# Sch.net
KiCad netlist of a schematic drawn in Altium Designer
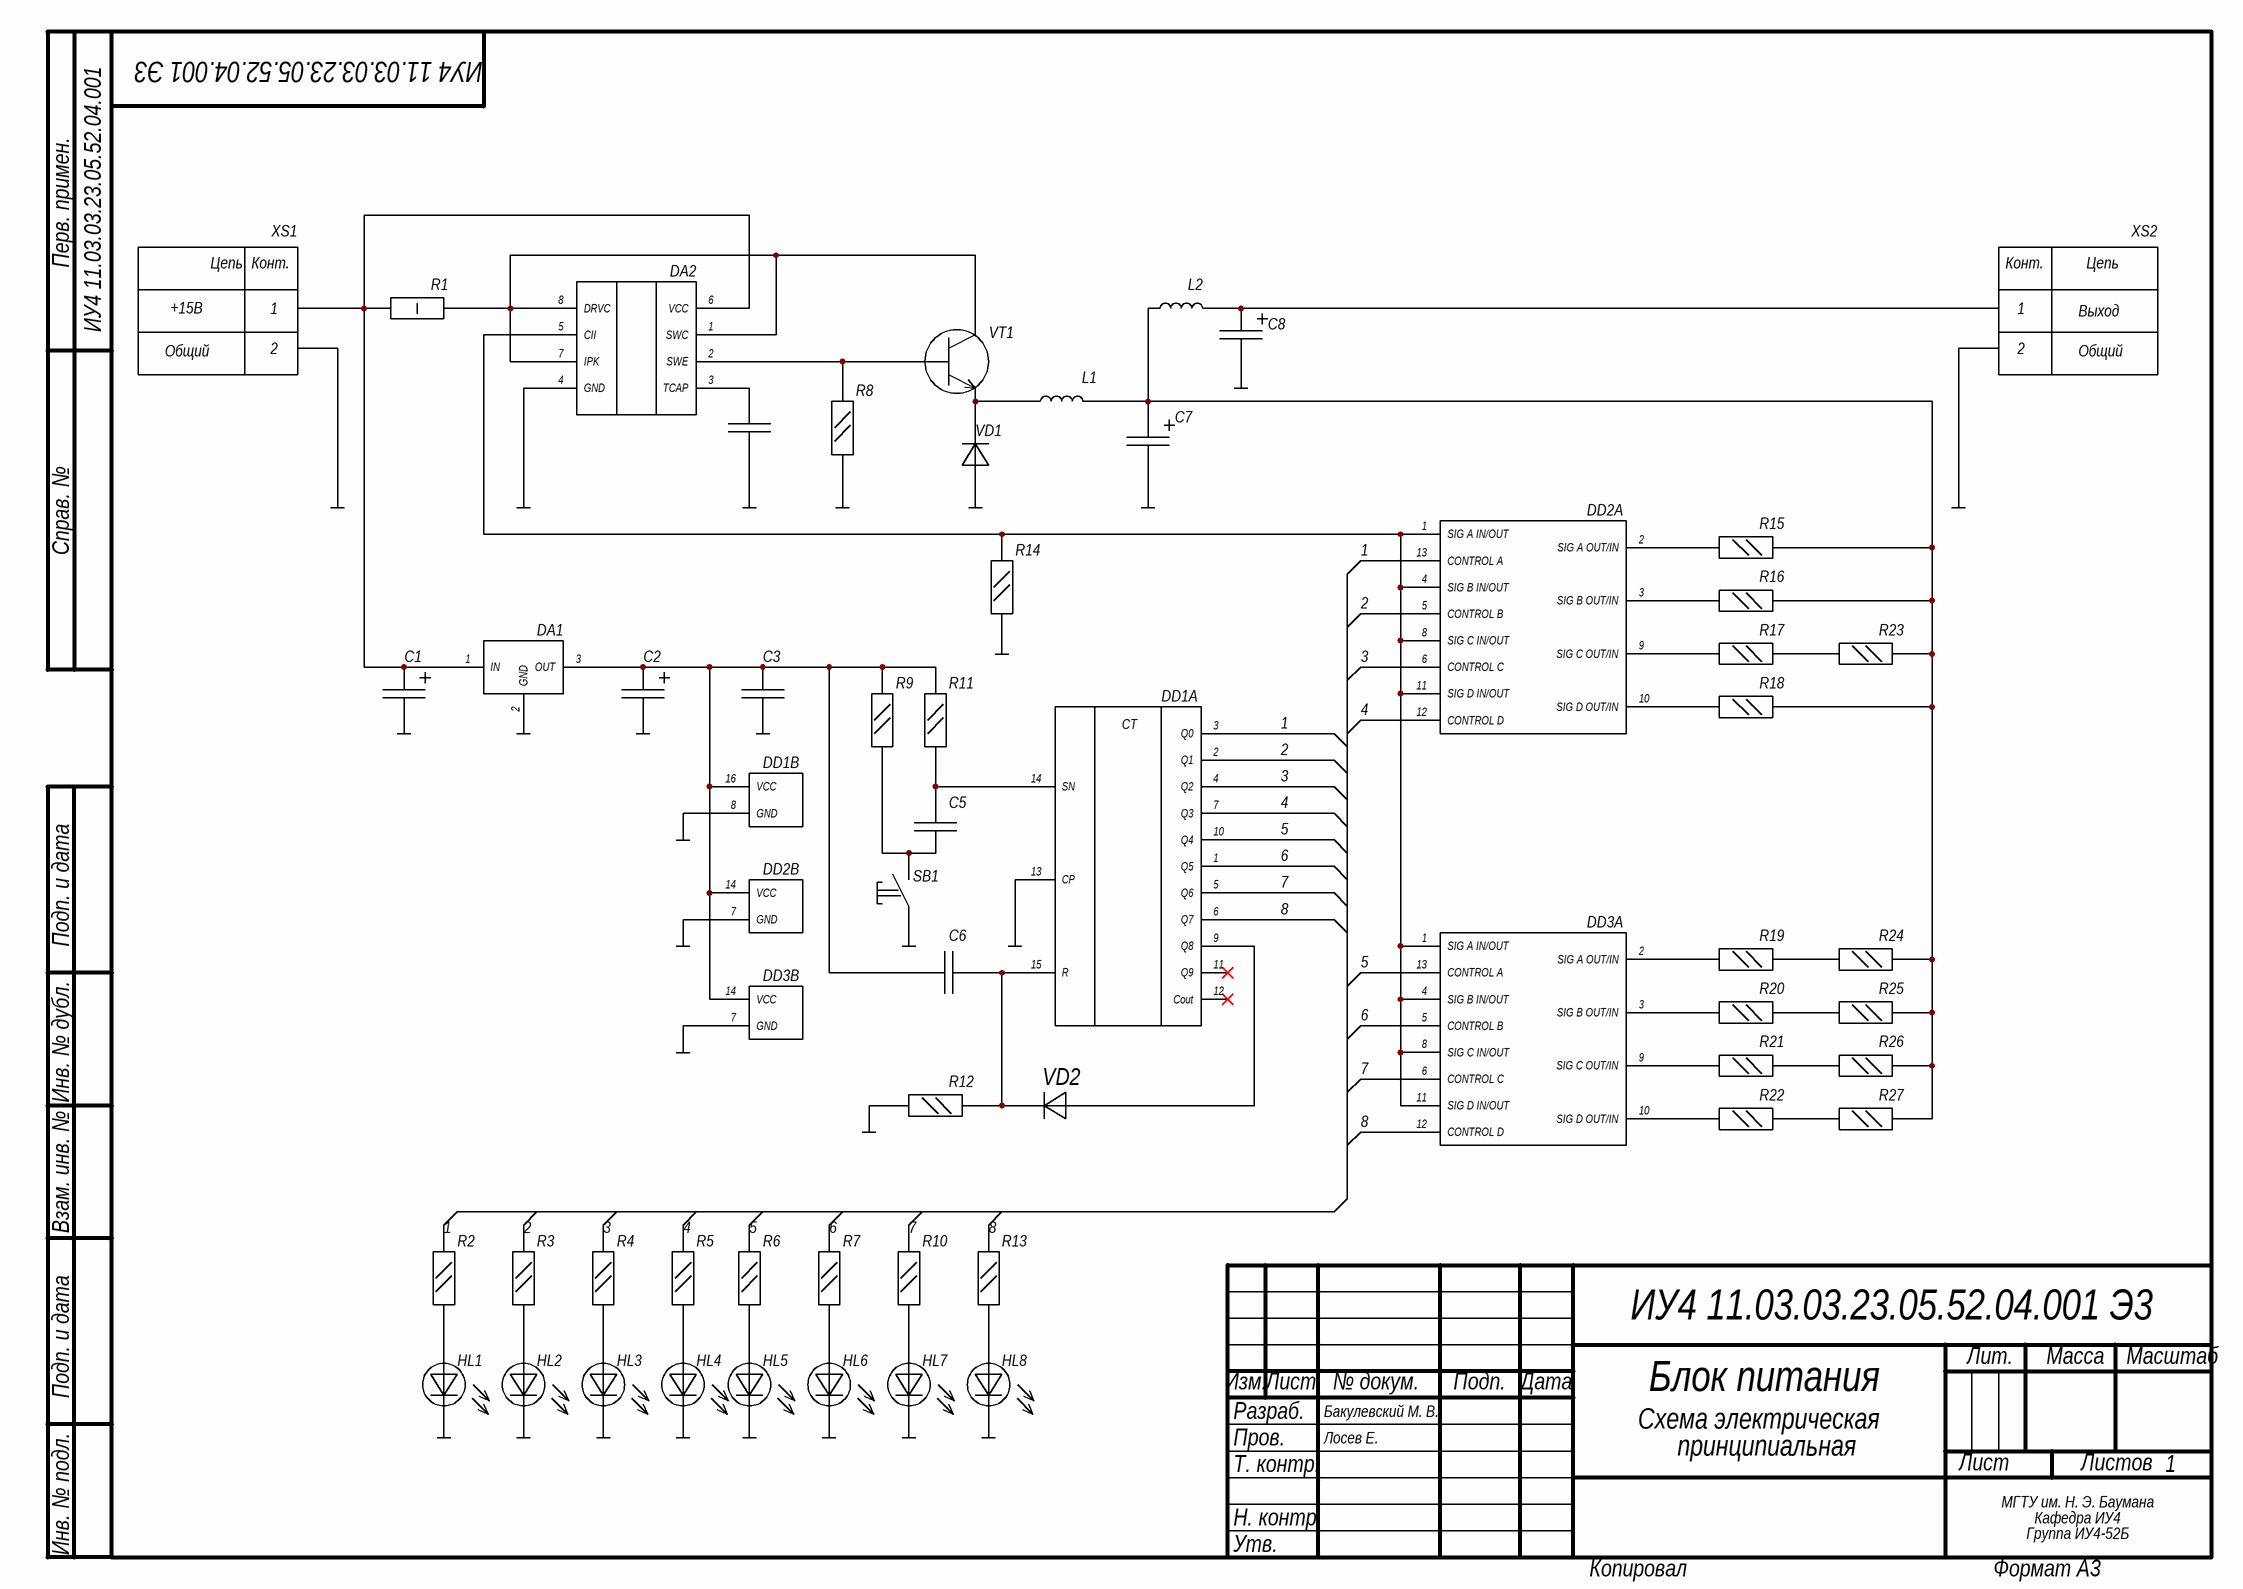
[diagram p0: Sch.SchDoc]

(export (version "E")
  (design (tool "Eeschema 10.0.6"))
  (components
    (comp (ref "C1")
      (value "100uF 25V")
      (footprint "CAPPR250-630X1120")
      (description "ECAP TKR101M1EE11 25В 100мкФ ±5% (Jamicon, Китай)")
      (libsource (lib "Schlib1") (part "Cap Polarity 100uF 25V"))
    )
    (comp (ref "C2")
      (value "100uF 25V")
      (footprint "CAPPR250-630X1120")
      (description "ECAP TKR101M1EE11 25В 100мкФ ±5% (Jamicon, Китай)")
      (libsource (lib "Schlib1") (part "Cap Polarity 100uF 25V"))
    )
    (comp (ref "C3")
      (value "Cap Ceramic 0.1uF")
      (footprint "CAPPRB508-450X850")
      (description "CAP X7R RDER71H104K 25В 0.1мкФ ±10% (Murata, Япония)")
      (libsource (lib "Schlib1") (part "Cap Ceramic 0.1uF"))
    )
    (comp (ref "C4")
      (value "Cap Ceramic 470pF")
      (footprint "CAPPRB508-450X850")
      (description "CAP NPO RDE5C1H471J 25В 470пкФ ±5% (Murata, Япония)")
      (libsource (lib "Schlib1") (part "Cap Ceramic 470pF"))
    )
    (comp (ref "C5")
      (value "Cap Ceramic 0.1uF")
      (footprint "CAPPRB508-450X850")
      (description "CAP X7R RDER71H104K 25В 0.1мкФ ±10% (Murata, Япония)")
      (libsource (lib "Schlib1") (part "Cap Ceramic 0.1uF"))
    )
    (comp (ref "C6")
      (value "Cap Ceramic 0.1uF")
      (footprint "CAPPRB508-450X850")
      (description "CAP X7R RDER71H104K 25В 0.1мкФ ±10% (Murata, Япония)")
      (libsource (lib "Schlib1") (part "Cap Ceramic 0.1uF"))
    )
    (comp (ref "C7")
      (value "470uF 25V")
      (footprint "CAPPR350-850X1300")
      (description "ECAP TKR471M1EF14 25В 470мкФ ±5% (Jamicon, Китай)")
      (libsource (lib "Schlib1") (part "Cap Polarity 470uF 25V"))
    )
    (comp (ref "C8")
      (value "470uF 25V")
      (footprint "CAPPR350-850X1300")
      (description "ECAP TKR471M1EF14 25В 470мкФ ±5% (Jamicon, Китай)")
      (libsource (lib "Schlib1") (part "Cap Polarity 470uF 25V"))
    )
    (comp (ref "DA1")
      (value "L7809ABV")
      (footprint "TO-220AB")
      (description "L7809ABV (STMicroelectronics, Швейцария)")
      (libsource (lib "Schlib1") (part "L7809ABV"))
    )
    (comp (ref "DA2")
      (value "MC34063ABN")
      (footprint "DIPS8-300")
      (description "MC34063ABN (STMicroelectronis, Швейцария)")
      (libsource (lib "Schlib1") (part "MC34063ABN"))
    )
    (comp (ref "DD1")
      (value "CD4017BE")
      (footprint "DIPS16-300")
      (description "CD4017BE (Texas Instuments, США)")
      (libsource (lib "Schlib1") (part "CD4017BE"))
    )
    (comp (ref "DD2")
      (value "CD4066BE")
      (footprint "DIPS14-300")
      (description "CD4066BE (HGSEMI, Китай)")
      (libsource (lib "Schlib1") (part "CD4066BE"))
    )
    (comp (ref "DD3")
      (value "CD4066BE")
      (footprint "DIPS14-300")
      (description "CD4066BE (HGSEMI, Китай)")
      (libsource (lib "Schlib1") (part "CD4066BE"))
    )
    (comp (ref "HL1")
      (value "LED Red")
      (footprint "LD-5mm-R")
      (description "GNL-5012ED (G-nor Electronics, Китай)")
      (libsource (lib "Schlib1") (part "LED Red"))
    )
    (comp (ref "HL2")
      (value "LED Red")
      (footprint "LD-5mm-R")
      (description "GNL-5012ED (G-nor Electronics, Китай)")
      (libsource (lib "Schlib1") (part "LED Red"))
    )
    (comp (ref "HL3")
      (value "LED Red")
      (footprint "LD-5mm-R")
      (description "GNL-5012ED (G-nor Electronics, Китай)")
      (libsource (lib "Schlib1") (part "LED Red"))
    )
    (comp (ref "HL4")
      (value "LED Red")
      (footprint "LD-5mm-R")
      (description "GNL-5012ED (G-nor Electronics, Китай)")
      (libsource (lib "Schlib1") (part "LED Red"))
    )
    (comp (ref "HL5")
      (value "LED Red")
      (footprint "LD-5mm-R")
      (description "GNL-5012ED (G-nor Electronics, Китай)")
      (libsource (lib "Schlib1") (part "LED Red"))
    )
    (comp (ref "HL6")
      (value "LED Red")
      (footprint "LD-5mm-R")
      (description "GNL-5012ED (G-nor Electronics, Китай)")
      (libsource (lib "Schlib1") (part "LED Red"))
    )
    (comp (ref "HL7")
      (value "LED Red")
      (footprint "LD-5mm-R")
      (description "GNL-5012ED (G-nor Electronics, Китай)")
      (libsource (lib "Schlib1") (part "LED Red"))
    )
    (comp (ref "HL8")
      (value "LED Red")
      (footprint "LD-5mm-R")
      (description "GNL-5012ED (G-nor Electronics, Китай)")
      (libsource (lib "Schlib1") (part "LED Red"))
    )
    (comp (ref "L1")
      (value "КИ (КИГ) 3,0−100мкГн ±5%")
      (footprint "INDRD_WURTH_WE-TI")
      (description "КИ (КИГ) 3,0−100мкГн ±10% (Россия)")
      (libsource (lib "Schlib1") (part "Inductor КИ (КИГ) 3,0−100мкГн ±5%"))
    )
    (comp (ref "L2")
      (value "КИ (КИГ) 3,0−100мкГн ±5%")
      (footprint "INDRD_WURTH_WE-TI")
      (description "КИ (КИГ) 3,0−100мкГн ±10% (Россия)")
      (libsource (lib "Schlib1") (part "Inductor КИ (КИГ) 3,0−100мкГн ±5%"))
    )
    (comp (ref "R1")
      (value "0,1Ом")
      (footprint "Res 1W")
      (description "С1-4−1−0,1Ом ±5% (Россия)")
      (libsource (lib "Schlib1") (part "Res 0,1 1W"))
    )
    (comp (ref "R2")
      (value "1кОм")
      (footprint "Res 0.125W")
      (description "С1-4−0,125−1кОм ±5% (Россия)")
      (libsource (lib "Schlib1") (part "Res 1K 0.125W"))
    )
    (comp (ref "R3")
      (value "1кОм")
      (footprint "Res 0.125W")
      (description "С1-4−0,125−1кОм ±5% (Россия)")
      (libsource (lib "Schlib1") (part "Res 1K 0.125W"))
    )
    (comp (ref "R4")
      (value "1кОм")
      (footprint "Res 0.125W")
      (description "С1-4−0,125−1кОм ±5% (Россия)")
      (libsource (lib "Schlib1") (part "Res 1K 0.125W"))
    )
    (comp (ref "R5")
      (value "1кОм")
      (footprint "Res 0.125W")
      (description "С1-4−0,125−1кОм ±5% (Россия)")
      (libsource (lib "Schlib1") (part "Res 1K 0.125W"))
    )
    (comp (ref "R6")
      (value "1кОм")
      (footprint "Res 0.125W")
      (description "С1-4−0,125−1кОм ±5% (Россия)")
      (libsource (lib "Schlib1") (part "Res 1K 0.125W"))
    )
    (comp (ref "R7")
      (value "1кОм")
      (footprint "Res 0.125W")
      (description "С1-4−0,125−1кОм ±5% (Россия)")
      (libsource (lib "Schlib1") (part "Res 1K 0.125W"))
    )
    (comp (ref "R8")
      (value "22кОм")
      (footprint "Res 0.125W")
      (description "С1-4−0,125−22кОм ±5% (Россия)")
      (libsource (lib "Schlib1") (part "Res 22K 0.125W"))
    )
    (comp (ref "R9")
      (value "100кОм")
      (footprint "Res 0.125W")
      (description "С1-4−0,125−100кОм ±5% (Россия)")
      (libsource (lib "Schlib1") (part "Res 100K 0.125W"))
    )
    (comp (ref "R10")
      (value "1кОм")
      (footprint "Res 0.125W")
      (description "С1-4−0,125−1кОм ±5% (Россия)")
      (libsource (lib "Schlib1") (part "Res 1K 0.125W"))
    )
    (comp (ref "R11")
      (value "100кОм")
      (footprint "Res 0.125W")
      (description "С1-4−0,125−100кОм ±5% (Россия)")
      (libsource (lib "Schlib1") (part "Res 100K 0.125W"))
    )
    (comp (ref "R12")
      (value "100кОм")
      (footprint "Res 0.125W")
      (description "С1-4−0,125−100кОм ±5% (Россия)")
      (libsource (lib "Schlib1") (part "Res 100K 0.125W"))
    )
    (comp (ref "R13")
      (value "1кОм")
      (footprint "Res 0.125W")
      (description "С1-4−0,125−1кОм ±5% (Россия)")
      (libsource (lib "Schlib1") (part "Res 1K 0.125W"))
    )
    (comp (ref "R14")
      (value "1кОм")
      (footprint "Res 0.125W")
      (description "С1-4−0,125−1,5кОм ±5% (Россия)")
      (libsource (lib "Schlib1") (part "Res 1,5K 0.125W"))
    )
    (comp (ref "R15")
      (value "270Ом")
      (footprint "Res 0.125W")
      (description "С1-4−0,125−270Ом ±5% (Россия)")
      (libsource (lib "Schlib1") (part "Res 270 0.125W"))
    )
    (comp (ref "R16")
      (value "1кОм")
      (footprint "Res 0.125W")
      (description "С1-4−0,125−1,5кОм ±5% (Россия)")
      (libsource (lib "Schlib1") (part "Res 1,5K 0.125W"))
    )
    (comp (ref "R17")
      (value "2кОм")
      (footprint "Res 0.125W")
      (description "С1-4−0,125−2кОм ±5% (Россия)")
      (libsource (lib "Schlib1") (part "Res 2K 0.125W"))
    )
    (comp (ref "R18")
      (value "3,9кОм")
      (footprint "Res 0.125W")
      (description "С1-4−0,125−3,9кОм ±5% (Россия)")
      (libsource (lib "Schlib1") (part "Res 3,9K 0.125W"))
    )
    (comp (ref "R19")
      (value "4,3кОм")
      (footprint "Res 0.125W")
      (description "С1-4−0,125−4,3кОм ±5% (Россия)")
      (libsource (lib "Schlib1") (part "Res 4,3K 0.125W"))
    )
    (comp (ref "R20")
      (value "5,6кОм")
      (footprint "Res 0.125W")
      (description "С1-4−0,125−5,6кОм ±5% (Россия)")
      (libsource (lib "Schlib1") (part "Res 5,6K 0.125W"))
    )
    (comp (ref "R21")
      (value "7,5кОм")
      (footprint "Res 0.125W")
      (description "С1-4−0,125−7,5кОм ±5% (Россия)")
      (libsource (lib "Schlib1") (part "Res 7,5K 0.125W"))
    )
    (comp (ref "R22")
      (value "9,1кОм")
      (footprint "Res 0.125W")
      (description "С1-4−0,125−9,1кОм ±5% (Россия)")
      (libsource (lib "Schlib1") (part "Res 9,1K 0.125W"))
    )
    (comp (ref "R23")
      (value "100Ом")
      (footprint "Res 0.125W")
      (description "С1-4−0,125−100Ом ±5% (Россия)")
      (libsource (lib "Schlib1") (part "Res 100 0.125W"))
    )
    (comp (ref "R24")
      (value "200Ом")
      (footprint "Res 0.125W")
      (description "С1-4−0,125−200Ом ±5% (Россия)")
      (libsource (lib "Schlib1") (part "Res 200 0.125W"))
    )
    (comp (ref "R25")
      (value "200Ом")
      (footprint "Res 0.125W")
      (description "С1-4−0,125−200Ом ±5% (Россия)")
      (libsource (lib "Schlib1") (part "Res 200 0.125W"))
    )
    (comp (ref "R26")
      (value "100Ом")
      (footprint "Res 0.125W")
      (description "С1-4−0,125−100Ом ±5% (Россия)")
      (libsource (lib "Schlib1") (part "Res 100 0.125W"))
    )
    (comp (ref "R27")
      (value "300Ом")
      (footprint "Res 0.125W")
      (description "С1-4−0,125−300Ом ±5% (Россия)")
      (libsource (lib "Schlib1") (part "Res 300 0.125W"))
    )
    (comp (ref "SB1")
      (value "Button SMD")
      (footprint "Button SMD")
      (description "Кнопка тактовая 1437566-3 (TE Connectivity, США)")
      (libsource (lib "Schlib1") (part "Button"))
    )
    (comp (ref "VD1")
      (value "1N5820")
      (footprint "DO-27")
      (description "1N5820 (Diotec, Германия)")
      (libsource (lib "Schlib1") (part "Diode 1N5820"))
    )
    (comp (ref "VD2")
      (value "1N4002")
      (footprint "DO-35")
      (description "1N4148 (Diotec, Германия)")
      (fields (field (name "PUBLISHER") "Andrew Danich"))
      (libsource (lib "Schlib1") (part "Diode 1N4148"))
    )
    (comp (ref "VT1")
      (value "TIP121G")
      (footprint "TO-220AB")
      (description "TIP121G (ON Semiconductor, США)")
      (libsource (lib "Schlib1") (part "Transistor TIP121G"))
    )
    (comp (ref "XS1")
      (value "Power Connector 2 pin")
      (footprint "WIELAND_25.161.0253.0")
      (description "25.161.0253.0 (Wieland Electric, Германия)")
      (libsource (lib "Schlib1") (part "Power Connector 2 pin"))
    )
    (comp (ref "XS2")
      (value "Power Connector 2 pin")
      (footprint "WIELAND_25.161.0253.0")
      (description "25.161.0253.0 (Wieland Electric, Германия)")
      (libsource (lib "Schlib1") (part "Power Connector 2 pin"))
    )
  )
  (nets
    (net (code "1") (name "/1") (class "Default")
      (node (ref "DD1") (pin "3") (pinfunction "Q0_3") (pintype "passive"))
      (node (ref "DD2") (pin "13") (pinfunction "CONTROL_A_13") (pintype "passive"))
    )
    (net (code "2") (name "/2") (class "Default")
      (node (ref "DD1") (pin "2") (pinfunction "Q1_2") (pintype "passive"))
      (node (ref "DD2") (pin "5") (pinfunction "CONTROL_B_5") (pintype "passive"))
    )
    (net (code "3") (name "/3") (class "Default")
      (node (ref "DD1") (pin "4") (pinfunction "Q2_4") (pintype "passive"))
      (node (ref "DD2") (pin "6") (pinfunction "CONTROL_C_6") (pintype "passive"))
    )
    (net (code "4") (name "/4") (class "Default")
      (node (ref "DD1") (pin "7") (pinfunction "Q3_7") (pintype "passive"))
      (node (ref "DD2") (pin "12") (pinfunction "CONTROL_D_12") (pintype "passive"))
    )
    (net (code "5") (name "/5") (class "Default")
      (node (ref "DD1") (pin "10") (pinfunction "Q4_10") (pintype "passive"))
      (node (ref "DD3") (pin "13") (pinfunction "CONTROL_A_13") (pintype "passive"))
    )
    (net (code "6") (name "/6") (class "Default")
      (node (ref "DD1") (pin "1") (pinfunction "Q5_1") (pintype "passive"))
      (node (ref "DD3") (pin "5") (pinfunction "CONTROL_B_5") (pintype "passive"))
    )
    (net (code "7") (name "/7") (class "Default")
      (node (ref "DD1") (pin "5") (pinfunction "Q6_5") (pintype "passive"))
      (node (ref "DD3") (pin "6") (pinfunction "CONTROL_C_6") (pintype "passive"))
    )
    (net (code "8") (name "/8") (class "Default")
      (node (ref "DD1") (pin "6") (pinfunction "Q7_6") (pintype "passive"))
      (node (ref "DD3") (pin "12") (pinfunction "CONTROL_D_12") (pintype "passive"))
    )
    (net (code "9") (name "GND") (class "Default")
      (node (ref "C1") (pin "2") (pinfunction "2_2") (pintype "passive"))
      (node (ref "C2") (pin "2") (pinfunction "2_2") (pintype "passive"))
      (node (ref "C3") (pin "2") (pinfunction "2_2") (pintype "passive"))
      (node (ref "C4") (pin "2") (pinfunction "2_2") (pintype "passive"))
      (node (ref "C7") (pin "2") (pinfunction "2_2") (pintype "passive"))
      (node (ref "C8") (pin "2") (pinfunction "2_2") (pintype "passive"))
      (node (ref "DA1") (pin "2") (pinfunction "GND_2") (pintype "passive"))
      (node (ref "DA2") (pin "4") (pinfunction "GND_4") (pintype "passive"))
      (node (ref "DD1") (pin "13") (pinfunction "CP_13") (pintype "passive"))
      (node (ref "DD1") (pin "8") (pinfunction "GND_8") (pintype "passive"))
      (node (ref "DD2") (pin "7") (pinfunction "GND_7") (pintype "passive"))
      (node (ref "DD3") (pin "7") (pinfunction "GND_7") (pintype "passive"))
      (node (ref "HL1") (pin "2") (pinfunction "K_2") (pintype "passive"))
      (node (ref "HL2") (pin "2") (pinfunction "K_2") (pintype "passive"))
      (node (ref "HL3") (pin "2") (pinfunction "K_2") (pintype "passive"))
      (node (ref "HL4") (pin "2") (pinfunction "K_2") (pintype "passive"))
      (node (ref "HL5") (pin "2") (pinfunction "K_2") (pintype "passive"))
      (node (ref "HL6") (pin "2") (pinfunction "K_2") (pintype "passive"))
      (node (ref "HL7") (pin "2") (pinfunction "K_2") (pintype "passive"))
      (node (ref "HL8") (pin "2") (pinfunction "K_2") (pintype "passive"))
      (node (ref "R12") (pin "1") (pinfunction "1_1") (pintype "passive"))
      (node (ref "R14") (pin "1") (pinfunction "1_1") (pintype "passive"))
      (node (ref "R8") (pin "1") (pinfunction "1_1") (pintype "passive"))
      (node (ref "SB1") (pin "1") (pintype "passive"))
      (node (ref "VD1") (pin "1") (pinfunction "А_1") (pintype "passive"))
      (node (ref "XS1") (pin "2") (pinfunction "2_2") (pintype "passive"))
      (node (ref "XS2") (pin "2") (pinfunction "2_2") (pintype "passive"))
    )
    (net (code "10") (name "Net-(C5-Pad2)") (class "Default")
      (node (ref "C5") (pin "2") (pinfunction "2_2") (pintype "passive"))
      (node (ref "R9") (pin "1") (pinfunction "1_1") (pintype "passive"))
      (node (ref "SB1") (pin "2") (pintype "passive"))
    )
    (net (code "11") (name "Net-(C7-Pad1)") (class "Default")
      (node (ref "C7") (pin "1") (pinfunction "1_1") (pintype "passive"))
      (node (ref "L1") (pin "2") (pinfunction "2_2") (pintype "passive"))
      (node (ref "L2") (pin "1") (pinfunction "1_1") (pintype "passive"))
      (node (ref "R15") (pin "2") (pinfunction "2_2") (pintype "passive"))
      (node (ref "R16") (pin "2") (pinfunction "2_2") (pintype "passive"))
      (node (ref "R18") (pin "2") (pinfunction "2_2") (pintype "passive"))
      (node (ref "R23") (pin "2") (pinfunction "2_2") (pintype "passive"))
      (node (ref "R24") (pin "2") (pinfunction "2_2") (pintype "passive"))
      (node (ref "R25") (pin "2") (pinfunction "2_2") (pintype "passive"))
      (node (ref "R26") (pin "2") (pinfunction "2_2") (pintype "passive"))
      (node (ref "R27") (pin "2") (pinfunction "2_2") (pintype "passive"))
    )
    (net (code "12") (name "Net-(C8-Pad1)") (class "Default")
      (node (ref "C8") (pin "1") (pinfunction "1_1") (pintype "passive"))
      (node (ref "L2") (pin "2") (pinfunction "2_2") (pintype "passive"))
      (node (ref "XS2") (pin "1") (pinfunction "1_1") (pintype "passive"))
    )
    (net (code "13") (name "Net-(DA1-IN)") (class "Default")
      (node (ref "C1") (pin "1") (pinfunction "1_1") (pintype "passive"))
      (node (ref "DA1") (pin "1") (pinfunction "IN_1") (pintype "passive"))
      (node (ref "DA2") (pin "6") (pinfunction "VCC_6") (pintype "passive"))
      (node (ref "R1") (pin "2") (pinfunction "2_2") (pintype "passive"))
      (node (ref "XS1") (pin "1") (pinfunction "1_1") (pintype "passive"))
    )
    (net (code "14") (name "Net-(DA1-OUT)") (class "Default")
      (node (ref "C2") (pin "1") (pinfunction "1_1") (pintype "passive"))
      (node (ref "C3") (pin "1") (pinfunction "1_1") (pintype "passive"))
      (node (ref "C6") (pin "1") (pinfunction "1_1") (pintype "passive"))
      (node (ref "DA1") (pin "3") (pinfunction "OUT_3") (pintype "passive"))
      (node (ref "DD1") (pin "16") (pinfunction "VCC_16") (pintype "passive"))
      (node (ref "DD2") (pin "14") (pinfunction "VCC_14") (pintype "passive"))
      (node (ref "DD3") (pin "14") (pinfunction "VCC_14") (pintype "passive"))
      (node (ref "R11") (pin "2") (pinfunction "2_2") (pintype "passive"))
      (node (ref "R9") (pin "2") (pinfunction "2_2") (pintype "passive"))
    )
    (net (code "15") (name "Net-(DA2-CII)") (class "Default")
      (node (ref "DA2") (pin "5") (pinfunction "CII_5") (pintype "passive"))
      (node (ref "DD2") (pin "1") (pinfunction "SIG_A_IN/OUT_1") (pintype "passive"))
      (node (ref "DD2") (pin "11") (pinfunction "SIG_D_IN/OUT_11") (pintype "passive"))
      (node (ref "DD2") (pin "4") (pinfunction "SIG_B_IN/OUT_4") (pintype "passive"))
      (node (ref "DD2") (pin "8") (pinfunction "SIG_C_IN/OUT_8") (pintype "passive"))
      (node (ref "DD3") (pin "1") (pinfunction "SIG_A_IN/OUT_1") (pintype "passive"))
      (node (ref "DD3") (pin "11") (pinfunction "SIG_D_IN/OUT_11") (pintype "passive"))
      (node (ref "DD3") (pin "4") (pinfunction "SIG_B_IN/OUT_4") (pintype "passive"))
      (node (ref "DD3") (pin "8") (pinfunction "SIG_C_IN/OUT_8") (pintype "passive"))
      (node (ref "R14") (pin "2") (pinfunction "2_2") (pintype "passive"))
    )
    (net (code "16") (name "Net-(DA2-DRVC)") (class "Default")
      (node (ref "DA2") (pin "1") (pinfunction "SWC_1") (pintype "passive"))
      (node (ref "DA2") (pin "7") (pinfunction "IPK_7") (pintype "passive"))
      (node (ref "DA2") (pin "8") (pinfunction "DRVC_8") (pintype "passive"))
      (node (ref "R1") (pin "1") (pinfunction "1_1") (pintype "passive"))
      (node (ref "VT1") (pin "2") (pinfunction "К_2") (pintype "passive"))
    )
    (net (code "17") (name "Net-(DA2-SWE)") (class "Default")
      (node (ref "DA2") (pin "2") (pinfunction "SWE_2") (pintype "passive"))
      (node (ref "R8") (pin "2") (pinfunction "2_2") (pintype "passive"))
      (node (ref "VT1") (pin "1") (pinfunction "Б_1") (pintype "passive"))
    )
    (net (code "18") (name "Net-(DA2-TCAP)") (class "Default")
      (node (ref "C4") (pin "1") (pinfunction "1_1") (pintype "passive"))
      (node (ref "DA2") (pin "3") (pinfunction "TCAP_3") (pintype "passive"))
    )
    (net (code "19") (name "Net-(DD1A-Q8)") (class "Default")
      (node (ref "DD1") (pin "9") (pinfunction "Q8_9") (pintype "passive"))
      (node (ref "VD2") (pin "1") (pinfunction "А_1") (pintype "passive"))
    )
    (net (code "20") (name "Net-(DD1A-R)") (class "Default")
      (node (ref "C6") (pin "2") (pinfunction "2_2") (pintype "passive"))
      (node (ref "DD1") (pin "15") (pinfunction "R_15") (pintype "passive"))
      (node (ref "R12") (pin "2") (pinfunction "2_2") (pintype "passive"))
      (node (ref "VD2") (pin "2") (pinfunction "К_2") (pintype "passive"))
    )
    (net (code "21") (name "Net-(DD1A-SN)") (class "Default")
      (node (ref "C5") (pin "1") (pinfunction "1_1") (pintype "passive"))
      (node (ref "DD1") (pin "14") (pinfunction "SN_14") (pintype "passive"))
      (node (ref "R11") (pin "1") (pinfunction "1_1") (pintype "passive"))
    )
    (net (code "22") (name "Net-(DD2A-SIG_A_OUT{slash}IN)") (class "Default")
      (node (ref "DD2") (pin "2") (pinfunction "SIG_A_OUT/IN_2") (pintype "passive"))
      (node (ref "R15") (pin "1") (pinfunction "1_1") (pintype "passive"))
    )
    (net (code "23") (name "Net-(DD2A-SIG_B_OUT{slash}IN)") (class "Default")
      (node (ref "DD2") (pin "3") (pinfunction "SIG_B_OUT/IN_3") (pintype "passive"))
      (node (ref "R16") (pin "1") (pinfunction "1_1") (pintype "passive"))
    )
    (net (code "24") (name "Net-(DD2A-SIG_C_OUT{slash}IN)") (class "Default")
      (node (ref "DD2") (pin "9") (pinfunction "SIG_C_OUT/IN_9") (pintype "passive"))
      (node (ref "R17") (pin "1") (pinfunction "1_1") (pintype "passive"))
    )
    (net (code "25") (name "Net-(DD2A-SIG_D_OUT{slash}IN)") (class "Default")
      (node (ref "DD2") (pin "10") (pinfunction "SIG_D_OUT/IN_10") (pintype "passive"))
      (node (ref "R18") (pin "1") (pinfunction "1_1") (pintype "passive"))
    )
    (net (code "26") (name "Net-(DD3A-SIG_A_OUT{slash}IN)") (class "Default")
      (node (ref "DD3") (pin "2") (pinfunction "SIG_A_OUT/IN_2") (pintype "passive"))
      (node (ref "R19") (pin "1") (pinfunction "1_1") (pintype "passive"))
    )
    (net (code "27") (name "Net-(DD3A-SIG_B_OUT{slash}IN)") (class "Default")
      (node (ref "DD3") (pin "3") (pinfunction "SIG_B_OUT/IN_3") (pintype "passive"))
      (node (ref "R20") (pin "1") (pinfunction "1_1") (pintype "passive"))
    )
    (net (code "28") (name "Net-(DD3A-SIG_C_OUT{slash}IN)") (class "Default")
      (node (ref "DD3") (pin "9") (pinfunction "SIG_C_OUT/IN_9") (pintype "passive"))
      (node (ref "R21") (pin "1") (pinfunction "1_1") (pintype "passive"))
    )
    (net (code "29") (name "Net-(DD3A-SIG_D_OUT{slash}IN)") (class "Default")
      (node (ref "DD3") (pin "10") (pinfunction "SIG_D_OUT/IN_10") (pintype "passive"))
      (node (ref "R22") (pin "1") (pinfunction "1_1") (pintype "passive"))
    )
    (net (code "30") (name "Net-(HL1-A)") (class "Default")
      (node (ref "HL1") (pin "1") (pinfunction "A_1") (pintype "passive"))
      (node (ref "R2") (pin "1") (pinfunction "1_1") (pintype "passive"))
    )
    (net (code "31") (name "Net-(HL2-A)") (class "Default")
      (node (ref "HL2") (pin "1") (pinfunction "A_1") (pintype "passive"))
      (node (ref "R3") (pin "1") (pinfunction "1_1") (pintype "passive"))
    )
    (net (code "32") (name "Net-(HL3-A)") (class "Default")
      (node (ref "HL3") (pin "1") (pinfunction "A_1") (pintype "passive"))
      (node (ref "R4") (pin "1") (pinfunction "1_1") (pintype "passive"))
    )
    (net (code "33") (name "Net-(HL4-A)") (class "Default")
      (node (ref "HL4") (pin "1") (pinfunction "A_1") (pintype "passive"))
      (node (ref "R5") (pin "1") (pinfunction "1_1") (pintype "passive"))
    )
    (net (code "34") (name "Net-(HL5-A)") (class "Default")
      (node (ref "HL5") (pin "1") (pinfunction "A_1") (pintype "passive"))
      (node (ref "R6") (pin "1") (pinfunction "1_1") (pintype "passive"))
    )
    (net (code "35") (name "Net-(HL6-A)") (class "Default")
      (node (ref "HL6") (pin "1") (pinfunction "A_1") (pintype "passive"))
      (node (ref "R7") (pin "1") (pinfunction "1_1") (pintype "passive"))
    )
    (net (code "36") (name "Net-(HL7-A)") (class "Default")
      (node (ref "HL7") (pin "1") (pinfunction "A_1") (pintype "passive"))
      (node (ref "R10") (pin "1") (pinfunction "1_1") (pintype "passive"))
    )
    (net (code "37") (name "Net-(HL8-A)") (class "Default")
      (node (ref "HL8") (pin "1") (pinfunction "A_1") (pintype "passive"))
      (node (ref "R13") (pin "1") (pinfunction "1_1") (pintype "passive"))
    )
    (net (code "38") (name "Net-(R17-Pad2)") (class "Default")
      (node (ref "R17") (pin "2") (pinfunction "2_2") (pintype "passive"))
      (node (ref "R23") (pin "1") (pinfunction "1_1") (pintype "passive"))
    )
    (net (code "39") (name "Net-(R19-Pad2)") (class "Default")
      (node (ref "R19") (pin "2") (pinfunction "2_2") (pintype "passive"))
      (node (ref "R24") (pin "1") (pinfunction "1_1") (pintype "passive"))
    )
    (net (code "40") (name "Net-(R20-Pad2)") (class "Default")
      (node (ref "R20") (pin "2") (pinfunction "2_2") (pintype "passive"))
      (node (ref "R25") (pin "1") (pinfunction "1_1") (pintype "passive"))
    )
    (net (code "41") (name "Net-(R21-Pad2)") (class "Default")
      (node (ref "R21") (pin "2") (pinfunction "2_2") (pintype "passive"))
      (node (ref "R26") (pin "1") (pinfunction "1_1") (pintype "passive"))
    )
    (net (code "42") (name "Net-(R22-Pad2)") (class "Default")
      (node (ref "R22") (pin "2") (pinfunction "2_2") (pintype "passive"))
      (node (ref "R27") (pin "1") (pinfunction "1_1") (pintype "passive"))
    )
    (net (code "43") (name "Net-(VD1-К)") (class "Default")
      (node (ref "L1") (pin "1") (pinfunction "1_1") (pintype "passive"))
      (node (ref "VD1") (pin "2") (pinfunction "К_2") (pintype "passive"))
      (node (ref "VT1") (pin "3") (pinfunction "Э_3") (pintype "passive"))
    )
    (net (code "44") (name "unconnected-(DD1A-Cout-Pad12)") (class "Default")
      (node (ref "DD1") (pin "12") (pinfunction "Cout_12") (pintype "passive+no_connect"))
    )
    (net (code "45") (name "unconnected-(DD1A-Q9-Pad11)") (class "Default")
      (node (ref "DD1") (pin "11") (pinfunction "Q9_11") (pintype "passive+no_connect"))
    )
    (net (code "46") (name "unconnected-(R2-Pad2)") (class "Default")
      (node (ref "R2") (pin "2") (pinfunction "2_2") (pintype "passive"))
    )
    (net (code "47") (name "unconnected-(R3-Pad2)") (class "Default")
      (node (ref "R3") (pin "2") (pinfunction "2_2") (pintype "passive"))
    )
    (net (code "48") (name "unconnected-(R4-Pad2)") (class "Default")
      (node (ref "R4") (pin "2") (pinfunction "2_2") (pintype "passive"))
    )
    (net (code "49") (name "unconnected-(R5-Pad2)") (class "Default")
      (node (ref "R5") (pin "2") (pinfunction "2_2") (pintype "passive"))
    )
    (net (code "50") (name "unconnected-(R6-Pad2)") (class "Default")
      (node (ref "R6") (pin "2") (pinfunction "2_2") (pintype "passive"))
    )
    (net (code "51") (name "unconnected-(R7-Pad2)") (class "Default")
      (node (ref "R7") (pin "2") (pinfunction "2_2") (pintype "passive"))
    )
    (net (code "52") (name "unconnected-(R10-Pad2)") (class "Default")
      (node (ref "R10") (pin "2") (pinfunction "2_2") (pintype "passive"))
    )
    (net (code "53") (name "unconnected-(R13-Pad2)") (class "Default")
      (node (ref "R13") (pin "2") (pinfunction "2_2") (pintype "passive"))
    )
  )
)
